# Relay-Timer.net
KiCad netlist of a schematic drawn in EAGLE
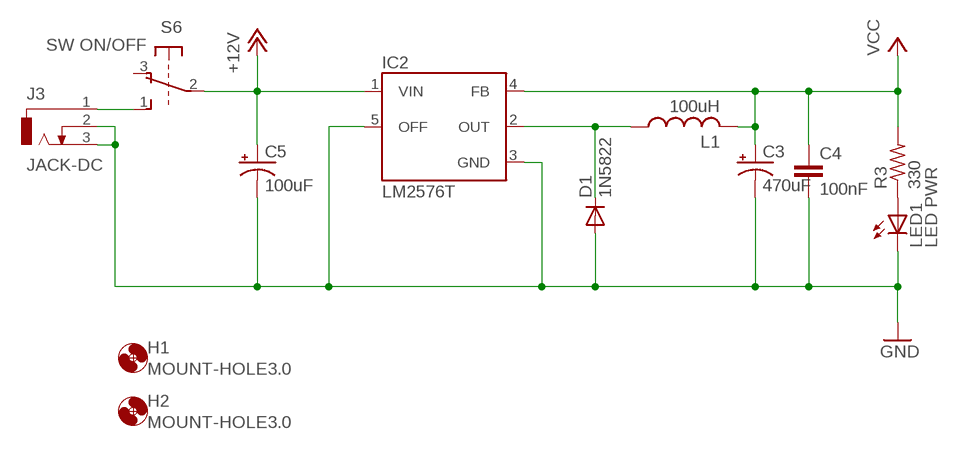
[diagram p0: schematic, sheet 1]
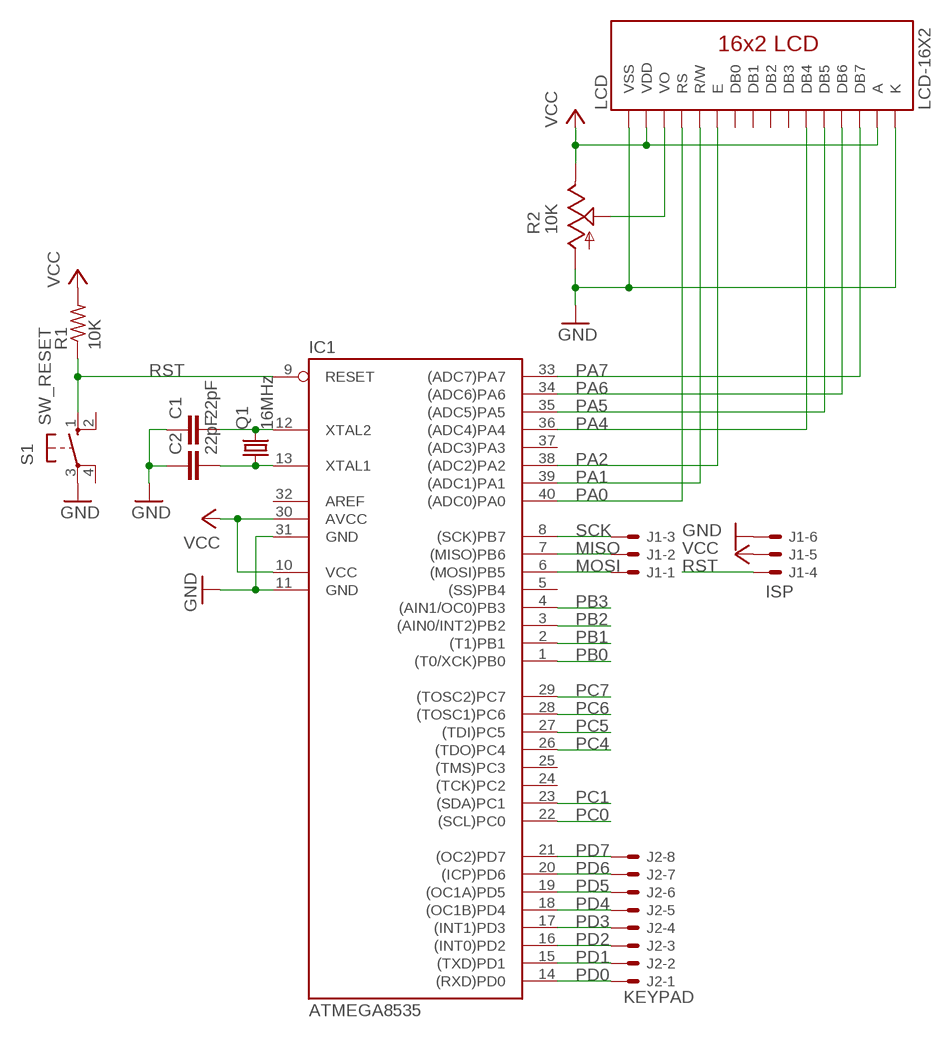
[diagram p1: schematic, sheet 2]
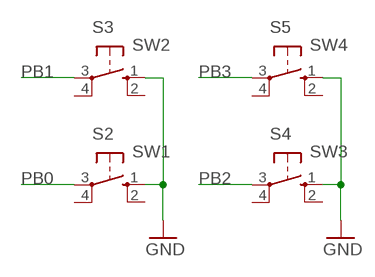
[diagram p2: schematic, sheet 3]
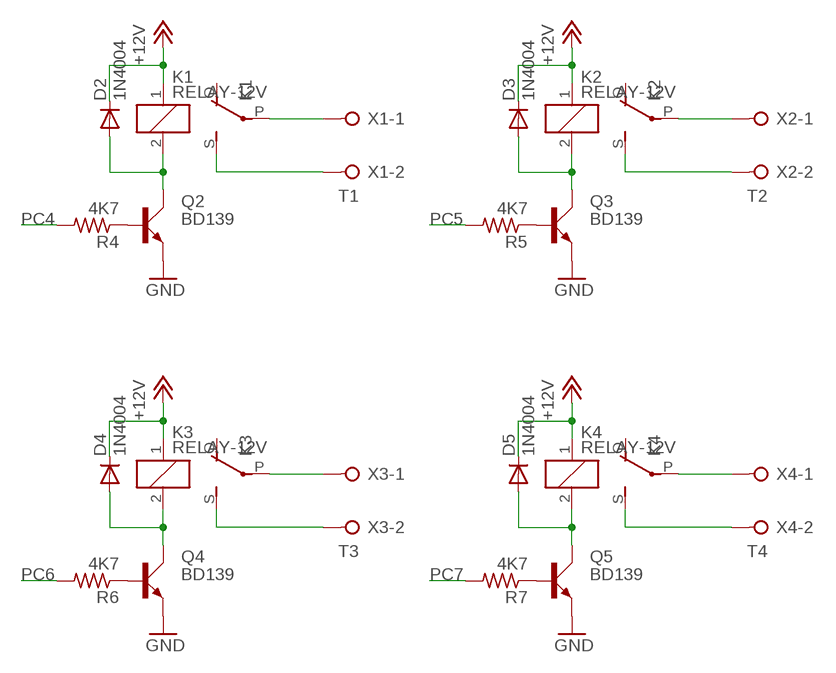
[diagram p3: schematic, sheet 4]
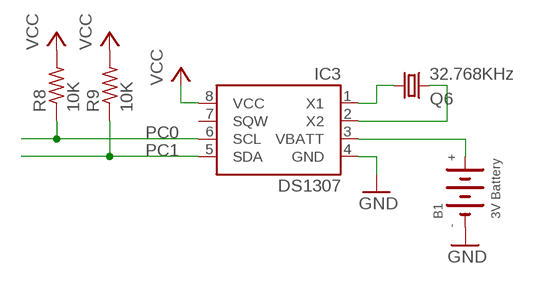
[diagram p4: schematic, sheet 5]

(export (version "E")
  (design (tool "Eeschema 10.0.6"))
  (components
    (comp (ref "C3")
      (value "470uF")
      (footprint "eagle-import:E3,5-8")
      (libsource (lib "eagle-import") (part "CAPACITOR-POLARE3.5-8"))
    )
    (comp (ref "C4")
      (value "100nF")
      (footprint "eagle-import:C025-024X044")
      (libsource (lib "eagle-import") (part "CAPACITOR-NONPOLAR025-024X044"))
    )
    (comp (ref "C5")
      (value "100uF")
      (footprint "eagle-import:E2,5-6")
      (libsource (lib "eagle-import") (part "CAPACITOR-POLARE2.5-6"))
    )
    (comp (ref "D1")
      (value "1N5822")
      (footprint "eagle-import:DO201-15")
      (libsource (lib "eagle-import") (part "DIODE-1N5822"))
    )
    (comp (ref "H1")
      (value "MOUNT-HOLE3.0")
      (footprint "eagle-import:3,0")
      (libsource (lib "eagle-import") (part "MOUNT-HOLE3.0"))
    )
    (comp (ref "H2")
      (value "MOUNT-HOLE3.0")
      (footprint "eagle-import:3,0")
      (libsource (lib "eagle-import") (part "MOUNT-HOLE3.0"))
    )
    (comp (ref "IC2")
      (value "LM2576T")
      (footprint "eagle-import:TO220-5")
      (libsource (lib "eagle-import") (part "LM2576T"))
    )
    (comp (ref "J3")
      (value "JACK-DC")
      (footprint "eagle-import:DCJ0202")
      (libsource (lib "eagle-import") (part "JACK-DC"))
    )
    (comp (ref "L1")
      (value "100uH")
      (footprint "eagle-import:TJ3-U2")
      (libsource (lib "eagle-import") (part "INDUCTORTJ3-U2"))
    )
    (comp (ref "LED1")
      (value "LED PWR")
      (footprint "eagle-import:LED3MM")
      (libsource (lib "eagle-import") (part "LED3MM"))
    )
    (comp (ref "R3")
      (value "330")
      (footprint "eagle-import:0204_7")
      (libsource (lib "eagle-import") (part "RESISTOR0204/7"))
    )
    (comp (ref "S6")
      (value "SW ON/OFF")
      (footprint "eagle-import:9077-2")
      (libsource (lib "eagle-import") (part "SWITCH-DETENT"))
    )
    (comp (ref "D2")
      (value "1N4004")
      (footprint "eagle-import:DO41-10")
      (libsource (lib "eagle-import") (part "DIODE-1N4004"))
    )
    (comp (ref "D3")
      (value "1N4004")
      (footprint "eagle-import:DO41-10")
      (libsource (lib "eagle-import") (part "DIODE-1N4004"))
    )
    (comp (ref "D4")
      (value "1N4004")
      (footprint "eagle-import:DO41-10")
      (libsource (lib "eagle-import") (part "DIODE-1N4004"))
    )
    (comp (ref "D5")
      (value "1N4004")
      (footprint "eagle-import:DO41-10")
      (libsource (lib "eagle-import") (part "DIODE-1N4004"))
    )
    (comp (ref "K1")
      (value "RELAY-12V")
      (footprint "eagle-import:G5LE")
      (libsource (lib "eagle-import") (part "G5L"))
    )
    (comp (ref "K2")
      (value "RELAY-12V")
      (footprint "eagle-import:G5LE")
      (libsource (lib "eagle-import") (part "G5L"))
    )
    (comp (ref "K3")
      (value "RELAY-12V")
      (footprint "eagle-import:G5LE")
      (libsource (lib "eagle-import") (part "G5L"))
    )
    (comp (ref "K4")
      (value "RELAY-12V")
      (footprint "eagle-import:G5LE")
      (libsource (lib "eagle-import") (part "G5L"))
    )
    (comp (ref "Q2")
      (value "BD139")
      (footprint "eagle-import:TO126AV")
      (libsource (lib "eagle-import") (part "BD139"))
    )
    (comp (ref "Q3")
      (value "BD139")
      (footprint "eagle-import:TO126AV")
      (libsource (lib "eagle-import") (part "BD139"))
    )
    (comp (ref "Q4")
      (value "BD139")
      (footprint "eagle-import:TO126AV")
      (libsource (lib "eagle-import") (part "BD139"))
    )
    (comp (ref "Q5")
      (value "BD139")
      (footprint "eagle-import:TO126AV")
      (libsource (lib "eagle-import") (part "BD139"))
    )
    (comp (ref "R4")
      (value "4K7")
      (footprint "eagle-import:0204_7")
      (libsource (lib "eagle-import") (part "RESISTOR0204/7"))
    )
    (comp (ref "R5")
      (value "4K7")
      (footprint "eagle-import:0204_7")
      (libsource (lib "eagle-import") (part "RESISTOR0204/7"))
    )
    (comp (ref "R6")
      (value "4K7")
      (footprint "eagle-import:0204_7")
      (libsource (lib "eagle-import") (part "RESISTOR0204/7"))
    )
    (comp (ref "R7")
      (value "4K7")
      (footprint "eagle-import:0204_7")
      (libsource (lib "eagle-import") (part "RESISTOR0204/7"))
    )
    (comp (ref "X1")
      (value "T1")
      (footprint "eagle-import:W237-132")
      (libsource (lib "eagle-import") (part "W237-02P"))
    )
    (comp (ref "X2")
      (value "T2")
      (footprint "eagle-import:W237-132")
      (libsource (lib "eagle-import") (part "W237-02P"))
    )
    (comp (ref "X3")
      (value "T3")
      (footprint "eagle-import:W237-132")
      (libsource (lib "eagle-import") (part "W237-02P"))
    )
    (comp (ref "X4")
      (value "T4")
      (footprint "eagle-import:W237-132")
      (libsource (lib "eagle-import") (part "W237-02P"))
    )
    (comp (ref "S2")
      (value "SW1")
      (footprint "eagle-import:B3F-10XX")
      (fields (field (name "MPN") "B3F-1000"))
      (libsource (lib "eagle-import") (part "SW-PUSHBUTTON"))
    )
    (comp (ref "S3")
      (value "SW2")
      (footprint "eagle-import:B3F-10XX")
      (fields (field (name "MPN") "B3F-1000"))
      (libsource (lib "eagle-import") (part "SW-PUSHBUTTON"))
    )
    (comp (ref "S4")
      (value "SW3")
      (footprint "eagle-import:B3F-10XX")
      (fields (field (name "MPN") "B3F-1000"))
      (libsource (lib "eagle-import") (part "SW-PUSHBUTTON"))
    )
    (comp (ref "S5")
      (value "SW4")
      (footprint "eagle-import:B3F-10XX")
      (fields (field (name "MPN") "B3F-1000"))
      (libsource (lib "eagle-import") (part "SW-PUSHBUTTON"))
    )
    (comp (ref "B1")
      (value "3V Battery")
      (footprint "eagle-import:CR2032")
      (libsource (lib "eagle-import") (part "BATTERYCR2032"))
    )
    (comp (ref "IC3")
      (value "DS1307")
      (footprint "eagle-import:DIP08")
      (libsource (lib "eagle-import") (part "DS1307"))
    )
    (comp (ref "Q6")
      (value "32.768KHz")
      (footprint "eagle-import:TC26H")
      (libsource (lib "eagle-import") (part "crystal_CRYSTALTC26H"))
    )
    (comp (ref "R8")
      (value "10K")
      (footprint "eagle-import:0204_7")
      (libsource (lib "eagle-import") (part "RESISTOR0204/7"))
    )
    (comp (ref "R9")
      (value "10K")
      (footprint "eagle-import:0204_7")
      (libsource (lib "eagle-import") (part "RESISTOR0204/7"))
    )
    (comp (ref "C1")
      (value "22pF")
      (footprint "eagle-import:C025-024X044")
      (libsource (lib "eagle-import") (part "CAPACITOR-NONPOLAR025-024X044"))
    )
    (comp (ref "C2")
      (value "22pF")
      (footprint "eagle-import:C025-024X044")
      (libsource (lib "eagle-import") (part "CAPACITOR-NONPOLAR025-024X044"))
    )
    (comp (ref "IC1")
      (value "ATMEGA8535")
      (footprint "eagle-import:DIL40")
      (fields (field (name "MPN") "ATMEGA32-16PU"))
      (libsource (lib "eagle-import") (part "ATMEGA8535/16/32"))
    )
    (comp (ref "J1")
      (value "ISP")
      (footprint "eagle-import:6410-06")
      (libsource (lib "eagle-import") (part "CON_MOLEX-?-0627-2061"))
    )
    (comp (ref "J2")
      (value "KEYPAD")
      (footprint "eagle-import:6410-08")
      (libsource (lib "eagle-import") (part "CON_MOLEX-?-0827-2081"))
    )
    (comp (ref "LCD")
      (value "LCD-16X2")
      (footprint "eagle-import:LCD-16X2")
      (libsource (lib "eagle-import") (part "LCD-16X2"))
    )
    (comp (ref "Q1")
      (value "16MHz")
      (footprint "eagle-import:HC49_S")
      (libsource (lib "eagle-import") (part "CRYSTALHC49S"))
    )
    (comp (ref "R1")
      (value "10K")
      (footprint "eagle-import:0204_7")
      (libsource (lib "eagle-import") (part "RESISTOR0204/7"))
    )
    (comp (ref "R2")
      (value "10K")
      (footprint "eagle-import:CA6V")
      (libsource (lib "eagle-import") (part "TRIMPOTCA6V"))
    )
    (comp (ref "S1")
      (value "SW_RESET")
      (footprint "eagle-import:B3F-10XX")
      (fields (field (name "MPN") "B3F-1000"))
      (libsource (lib "eagle-import") (part "SW-PUSHBUTTON"))
    )
  )
  (nets
    (net (code "1") (name "+12V") (class "Default")
      (node (ref "C5") (pin "+") (pinfunction "+_+") (pintype "passive"))
      (node (ref "D2") (pin "C") (pinfunction "C_C") (pintype "passive"))
      (node (ref "D3") (pin "C") (pinfunction "C_C") (pintype "passive"))
      (node (ref "D4") (pin "C") (pinfunction "C_C") (pintype "passive"))
      (node (ref "D5") (pin "C") (pinfunction "C_C") (pintype "passive"))
      (node (ref "IC2") (pin "1") (pinfunction "VIN_1") (pintype "power_in"))
      (node (ref "K1") (pin "1") (pinfunction "1_1") (pintype "passive"))
      (node (ref "K2") (pin "1") (pinfunction "1_1") (pintype "passive"))
      (node (ref "K3") (pin "1") (pinfunction "1_1") (pintype "passive"))
      (node (ref "K4") (pin "1") (pinfunction "1_1") (pintype "passive"))
      (node (ref "S6") (pin "2") (pinfunction "P_2") (pintype "passive"))
    )
    (net (code "2") (name "GND") (class "Default")
      (node (ref "B1") (pin "-") (pinfunction "-_-") (pintype "passive"))
      (node (ref "C1") (pin "1") (pinfunction "1_1") (pintype "passive"))
      (node (ref "C2") (pin "1") (pinfunction "1_1") (pintype "passive"))
      (node (ref "C3") (pin "-") (pinfunction "-_-") (pintype "passive"))
      (node (ref "C4") (pin "2") (pinfunction "2_2") (pintype "passive"))
      (node (ref "C5") (pin "-") (pinfunction "-_-") (pintype "passive"))
      (node (ref "D1") (pin "A") (pinfunction "A_A") (pintype "passive"))
      (node (ref "IC1") (pin "11") (pinfunction "GND_11") (pintype "power_in"))
      (node (ref "IC1") (pin "31") (pinfunction "GND_31") (pintype "power_in"))
      (node (ref "IC2") (pin "3") (pinfunction "GND_3") (pintype "power_in"))
      (node (ref "IC2") (pin "5") (pinfunction "OFF_5") (pintype "input"))
      (node (ref "IC3") (pin "4") (pinfunction "GND_4") (pintype "bidirectional"))
      (node (ref "J1") (pin "6") (pinfunction "S_6") (pintype "passive"))
      (node (ref "J3") (pin "2") (pinfunction "2_2") (pintype "passive"))
      (node (ref "J3") (pin "3") (pinfunction "3_3") (pintype "passive"))
      (node (ref "LCD") (pin "1") (pinfunction "VSS_1") (pintype "power_in"))
      (node (ref "LCD") (pin "16") (pinfunction "K_16") (pintype "power_in"))
      (node (ref "LED1") (pin "K") (pinfunction "C_K") (pintype "passive"))
      (node (ref "Q2") (pin "E") (pinfunction "E_E") (pintype "passive"))
      (node (ref "Q3") (pin "E") (pinfunction "E_E") (pintype "passive"))
      (node (ref "Q4") (pin "E") (pinfunction "E_E") (pintype "passive"))
      (node (ref "Q5") (pin "E") (pinfunction "E_E") (pintype "passive"))
      (node (ref "R2") (pin "A") (pinfunction "A_A") (pintype "passive"))
      (node (ref "S1") (pin "3") (pinfunction "P_3") (pintype "passive"))
      (node (ref "S2") (pin "1") (pinfunction "S_1") (pintype "passive"))
      (node (ref "S3") (pin "1") (pinfunction "S_1") (pintype "passive"))
      (node (ref "S4") (pin "1") (pinfunction "S_1") (pintype "passive"))
      (node (ref "S5") (pin "1") (pinfunction "S_1") (pintype "passive"))
    )
    (net (code "3") (name "MISO") (class "Default")
      (node (ref "IC1") (pin "7") (pinfunction "(MISO)PB6_7") (pintype "bidirectional"))
      (node (ref "J1") (pin "2") (pinfunction "S_2") (pintype "passive"))
    )
    (net (code "4") (name "MOSI") (class "Default")
      (node (ref "IC1") (pin "6") (pinfunction "(MOSI)PB5_6") (pintype "bidirectional"))
      (node (ref "J1") (pin "1") (pinfunction "S_1") (pintype "passive"))
    )
    (net (code "5") (name "Net-(D2-PadA)") (class "Default")
      (node (ref "D2") (pin "A") (pinfunction "A_A") (pintype "passive"))
      (node (ref "K1") (pin "2") (pinfunction "2_2") (pintype "passive"))
      (node (ref "Q2") (pin "C") (pinfunction "C_C") (pintype "passive"))
    )
    (net (code "6") (name "Net-(D3-PadA)") (class "Default")
      (node (ref "D3") (pin "A") (pinfunction "A_A") (pintype "passive"))
      (node (ref "K2") (pin "2") (pinfunction "2_2") (pintype "passive"))
      (node (ref "Q3") (pin "C") (pinfunction "C_C") (pintype "passive"))
    )
    (net (code "7") (name "Net-(D4-PadA)") (class "Default")
      (node (ref "D4") (pin "A") (pinfunction "A_A") (pintype "passive"))
      (node (ref "K3") (pin "2") (pinfunction "2_2") (pintype "passive"))
      (node (ref "Q4") (pin "C") (pinfunction "C_C") (pintype "passive"))
    )
    (net (code "8") (name "Net-(D5-PadA)") (class "Default")
      (node (ref "D5") (pin "A") (pinfunction "A_A") (pintype "passive"))
      (node (ref "K4") (pin "2") (pinfunction "2_2") (pintype "passive"))
      (node (ref "Q5") (pin "C") (pinfunction "C_C") (pintype "passive"))
    )
    (net (code "9") (name "Net-(IC1-XTAL1)") (class "Default")
      (node (ref "C2") (pin "2") (pinfunction "2_2") (pintype "passive"))
      (node (ref "IC1") (pin "13") (pinfunction "XTAL1_13") (pintype "bidirectional"))
      (node (ref "Q1") (pin "1") (pinfunction "1_1") (pintype "passive"))
    )
    (net (code "10") (name "Net-(IC1-XTAL2)") (class "Default")
      (node (ref "C1") (pin "2") (pinfunction "2_2") (pintype "passive"))
      (node (ref "IC1") (pin "12") (pinfunction "XTAL2_12") (pintype "bidirectional"))
      (node (ref "Q1") (pin "2") (pinfunction "2_2") (pintype "passive"))
    )
    (net (code "11") (name "Net-(IC2-OUT)") (class "Default")
      (node (ref "D1") (pin "C") (pinfunction "C_C") (pintype "passive"))
      (node (ref "IC2") (pin "2") (pinfunction "OUT_2") (pintype "output"))
      (node (ref "L1") (pin "1") (pinfunction "1_1") (pintype "passive"))
    )
    (net (code "12") (name "Net-(IC3-VBATT)") (class "Default")
      (node (ref "B1") (pin "+") (pinfunction "+_+") (pintype "passive"))
      (node (ref "IC3") (pin "3") (pinfunction "VBATT_3") (pintype "bidirectional"))
    )
    (net (code "13") (name "Net-(IC3-X1)") (class "Default")
      (node (ref "IC3") (pin "1") (pinfunction "X1_1") (pintype "bidirectional"))
      (node (ref "Q6") (pin "1") (pinfunction "1_1") (pintype "passive"))
    )
    (net (code "14") (name "Net-(IC3-X2)") (class "Default")
      (node (ref "IC3") (pin "2") (pinfunction "X2_2") (pintype "bidirectional"))
      (node (ref "Q6") (pin "2") (pinfunction "2_2") (pintype "passive"))
    )
    (net (code "15") (name "Net-(LCD-VO)") (class "Default")
      (node (ref "LCD") (pin "3") (pinfunction "VO_3") (pintype "bidirectional"))
      (node (ref "R2") (pin "S") (pinfunction "S_S") (pintype "passive"))
    )
    (net (code "16") (name "Net-(LED1-PadA)") (class "Default")
      (node (ref "LED1") (pin "A") (pinfunction "A_A") (pintype "passive"))
      (node (ref "R3") (pin "1") (pinfunction "1_1") (pintype "passive"))
    )
    (net (code "17") (name "Net-(Q2-PadB)") (class "Default")
      (node (ref "Q2") (pin "B") (pinfunction "B_B") (pintype "passive"))
      (node (ref "R4") (pin "1") (pinfunction "1_1") (pintype "passive"))
    )
    (net (code "18") (name "Net-(Q3-PadB)") (class "Default")
      (node (ref "Q3") (pin "B") (pinfunction "B_B") (pintype "passive"))
      (node (ref "R5") (pin "1") (pinfunction "1_1") (pintype "passive"))
    )
    (net (code "19") (name "Net-(Q4-PadB)") (class "Default")
      (node (ref "Q4") (pin "B") (pinfunction "B_B") (pintype "passive"))
      (node (ref "R6") (pin "1") (pinfunction "1_1") (pintype "passive"))
    )
    (net (code "20") (name "Net-(Q5-PadB)") (class "Default")
      (node (ref "Q5") (pin "B") (pinfunction "B_B") (pintype "passive"))
      (node (ref "R7") (pin "1") (pinfunction "1_1") (pintype "passive"))
    )
    (net (code "21") (name "Net-(S6-S)") (class "Default")
      (node (ref "J3") (pin "1") (pinfunction "1_1") (pintype "passive"))
      (node (ref "S6") (pin "1") (pinfunction "S_1") (pintype "passive"))
    )
    (net (code "22") (name "Net-(X1A-KL)") (class "Default")
      (node (ref "K1") (pin "P") (pinfunction "P_P") (pintype "passive"))
      (node (ref "X1") (pin "1") (pinfunction "KL_1") (pintype "passive"))
    )
    (net (code "23") (name "Net-(X1B-KL)") (class "Default")
      (node (ref "K1") (pin "S") (pinfunction "S_S") (pintype "passive"))
      (node (ref "X1") (pin "2") (pinfunction "KL_2") (pintype "passive"))
    )
    (net (code "24") (name "Net-(X2A-KL)") (class "Default")
      (node (ref "K2") (pin "P") (pinfunction "P_P") (pintype "passive"))
      (node (ref "X2") (pin "1") (pinfunction "KL_1") (pintype "passive"))
    )
    (net (code "25") (name "Net-(X2B-KL)") (class "Default")
      (node (ref "K2") (pin "S") (pinfunction "S_S") (pintype "passive"))
      (node (ref "X2") (pin "2") (pinfunction "KL_2") (pintype "passive"))
    )
    (net (code "26") (name "Net-(X3A-KL)") (class "Default")
      (node (ref "K3") (pin "P") (pinfunction "P_P") (pintype "passive"))
      (node (ref "X3") (pin "1") (pinfunction "KL_1") (pintype "passive"))
    )
    (net (code "27") (name "Net-(X3B-KL)") (class "Default")
      (node (ref "K3") (pin "S") (pinfunction "S_S") (pintype "passive"))
      (node (ref "X3") (pin "2") (pinfunction "KL_2") (pintype "passive"))
    )
    (net (code "28") (name "Net-(X4A-KL)") (class "Default")
      (node (ref "K4") (pin "P") (pinfunction "P_P") (pintype "passive"))
      (node (ref "X4") (pin "1") (pinfunction "KL_1") (pintype "passive"))
    )
    (net (code "29") (name "Net-(X4B-KL)") (class "Default")
      (node (ref "K4") (pin "S") (pinfunction "S_S") (pintype "passive"))
      (node (ref "X4") (pin "2") (pinfunction "KL_2") (pintype "passive"))
    )
    (net (code "30") (name "PA0") (class "Default")
      (node (ref "IC1") (pin "40") (pinfunction "(ADC0)PA0_40") (pintype "bidirectional"))
      (node (ref "LCD") (pin "4") (pinfunction "RS_4") (pintype "input"))
    )
    (net (code "31") (name "PA1") (class "Default")
      (node (ref "IC1") (pin "39") (pinfunction "(ADC1)PA1_39") (pintype "bidirectional"))
      (node (ref "LCD") (pin "5") (pinfunction "R/W_5") (pintype "input"))
    )
    (net (code "32") (name "PA2") (class "Default")
      (node (ref "IC1") (pin "38") (pinfunction "(ADC2)PA2_38") (pintype "bidirectional"))
      (node (ref "LCD") (pin "6") (pinfunction "E_6") (pintype "input"))
    )
    (net (code "33") (name "PA4") (class "Default")
      (node (ref "IC1") (pin "36") (pinfunction "(ADC4)PA4_36") (pintype "bidirectional"))
      (node (ref "LCD") (pin "11") (pinfunction "DB4_11") (pintype "bidirectional"))
    )
    (net (code "34") (name "PA5") (class "Default")
      (node (ref "IC1") (pin "35") (pinfunction "(ADC5)PA5_35") (pintype "bidirectional"))
      (node (ref "LCD") (pin "12") (pinfunction "DB5_12") (pintype "bidirectional"))
    )
    (net (code "35") (name "PA6") (class "Default")
      (node (ref "IC1") (pin "34") (pinfunction "(ADC6)PA6_34") (pintype "bidirectional"))
      (node (ref "LCD") (pin "13") (pinfunction "DB6_13") (pintype "bidirectional"))
    )
    (net (code "36") (name "PA7") (class "Default")
      (node (ref "IC1") (pin "33") (pinfunction "(ADC7)PA7_33") (pintype "bidirectional"))
      (node (ref "LCD") (pin "14") (pinfunction "DB7_14") (pintype "bidirectional"))
    )
    (net (code "37") (name "PB0") (class "Default")
      (node (ref "IC1") (pin "1") (pinfunction "(T0/XCK)PB0_1") (pintype "bidirectional"))
      (node (ref "S2") (pin "3") (pinfunction "P_3") (pintype "passive"))
    )
    (net (code "38") (name "PB1") (class "Default")
      (node (ref "IC1") (pin "2") (pinfunction "(T1)PB1_2") (pintype "bidirectional"))
      (node (ref "S3") (pin "3") (pinfunction "P_3") (pintype "passive"))
    )
    (net (code "39") (name "PB2") (class "Default")
      (node (ref "IC1") (pin "3") (pinfunction "(AIN0/INT2)PB2_3") (pintype "bidirectional"))
      (node (ref "S4") (pin "3") (pinfunction "P_3") (pintype "passive"))
    )
    (net (code "40") (name "PB3") (class "Default")
      (node (ref "IC1") (pin "4") (pinfunction "(AIN1/OC0)PB3_4") (pintype "bidirectional"))
      (node (ref "S5") (pin "3") (pinfunction "P_3") (pintype "passive"))
    )
    (net (code "41") (name "PC0") (class "Default")
      (node (ref "IC1") (pin "22") (pinfunction "(SCL)PC0_22") (pintype "bidirectional"))
      (node (ref "IC3") (pin "6") (pinfunction "SCL_6") (pintype "bidirectional"))
      (node (ref "R8") (pin "1") (pinfunction "1_1") (pintype "passive"))
    )
    (net (code "42") (name "PC1") (class "Default")
      (node (ref "IC1") (pin "23") (pinfunction "(SDA)PC1_23") (pintype "bidirectional"))
      (node (ref "IC3") (pin "5") (pinfunction "SDA_5") (pintype "bidirectional"))
      (node (ref "R9") (pin "1") (pinfunction "1_1") (pintype "passive"))
    )
    (net (code "43") (name "PC4") (class "Default")
      (node (ref "IC1") (pin "26") (pinfunction "(TDO)PC4_26") (pintype "bidirectional"))
      (node (ref "R4") (pin "2") (pinfunction "2_2") (pintype "passive"))
    )
    (net (code "44") (name "PC5") (class "Default")
      (node (ref "IC1") (pin "27") (pinfunction "(TDI)PC5_27") (pintype "bidirectional"))
      (node (ref "R5") (pin "2") (pinfunction "2_2") (pintype "passive"))
    )
    (net (code "45") (name "PC6") (class "Default")
      (node (ref "IC1") (pin "28") (pinfunction "(TOSC1)PC6_28") (pintype "bidirectional"))
      (node (ref "R6") (pin "2") (pinfunction "2_2") (pintype "passive"))
    )
    (net (code "46") (name "PC7") (class "Default")
      (node (ref "IC1") (pin "29") (pinfunction "(TOSC2)PC7_29") (pintype "bidirectional"))
      (node (ref "R7") (pin "2") (pinfunction "2_2") (pintype "passive"))
    )
    (net (code "47") (name "PD0") (class "Default")
      (node (ref "IC1") (pin "14") (pinfunction "(RXD)PD0_14") (pintype "bidirectional"))
      (node (ref "J2") (pin "1") (pinfunction "S_1") (pintype "passive"))
    )
    (net (code "48") (name "PD1") (class "Default")
      (node (ref "IC1") (pin "15") (pinfunction "(TXD)PD1_15") (pintype "bidirectional"))
      (node (ref "J2") (pin "2") (pinfunction "S_2") (pintype "passive"))
    )
    (net (code "49") (name "PD2") (class "Default")
      (node (ref "IC1") (pin "16") (pinfunction "(INT0)PD2_16") (pintype "bidirectional"))
      (node (ref "J2") (pin "3") (pinfunction "S_3") (pintype "passive"))
    )
    (net (code "50") (name "PD3") (class "Default")
      (node (ref "IC1") (pin "17") (pinfunction "(INT1)PD3_17") (pintype "bidirectional"))
      (node (ref "J2") (pin "4") (pinfunction "S_4") (pintype "passive"))
    )
    (net (code "51") (name "PD4") (class "Default")
      (node (ref "IC1") (pin "18") (pinfunction "(OC1B)PD4_18") (pintype "bidirectional"))
      (node (ref "J2") (pin "5") (pinfunction "S_5") (pintype "passive"))
    )
    (net (code "52") (name "PD5") (class "Default")
      (node (ref "IC1") (pin "19") (pinfunction "(OC1A)PD5_19") (pintype "bidirectional"))
      (node (ref "J2") (pin "6") (pinfunction "S_6") (pintype "passive"))
    )
    (net (code "53") (name "PD6") (class "Default")
      (node (ref "IC1") (pin "20") (pinfunction "(ICP)PD6_20") (pintype "bidirectional"))
      (node (ref "J2") (pin "7") (pinfunction "S_7") (pintype "passive"))
    )
    (net (code "54") (name "PD7") (class "Default")
      (node (ref "IC1") (pin "21") (pinfunction "(OC2)PD7_21") (pintype "bidirectional"))
      (node (ref "J2") (pin "8") (pinfunction "S_8") (pintype "passive"))
    )
    (net (code "55") (name "RST") (class "Default")
      (node (ref "IC1") (pin "9") (pinfunction "RESET_9") (pintype "input"))
      (node (ref "J1") (pin "4") (pinfunction "S_4") (pintype "passive"))
      (node (ref "R1") (pin "1") (pinfunction "1_1") (pintype "passive"))
      (node (ref "S1") (pin "1") (pinfunction "S_1") (pintype "passive"))
    )
    (net (code "56") (name "SCK") (class "Default")
      (node (ref "IC1") (pin "8") (pinfunction "(SCK)PB7_8") (pintype "bidirectional"))
      (node (ref "J1") (pin "3") (pinfunction "S_3") (pintype "passive"))
    )
    (net (code "57") (name "VCC") (class "Default")
      (node (ref "C3") (pin "+") (pinfunction "+_+") (pintype "passive"))
      (node (ref "C4") (pin "1") (pinfunction "1_1") (pintype "passive"))
      (node (ref "IC1") (pin "10") (pinfunction "VCC_10") (pintype "power_in"))
      (node (ref "IC1") (pin "30") (pinfunction "AVCC_30") (pintype "power_in"))
      (node (ref "IC2") (pin "4") (pinfunction "FB_4") (pintype "input"))
      (node (ref "IC3") (pin "8") (pinfunction "VCC_8") (pintype "bidirectional"))
      (node (ref "J1") (pin "5") (pinfunction "S_5") (pintype "passive"))
      (node (ref "L1") (pin "2") (pinfunction "2_2") (pintype "passive"))
      (node (ref "LCD") (pin "15") (pinfunction "A_15") (pintype "power_in"))
      (node (ref "LCD") (pin "2") (pinfunction "VDD_2") (pintype "power_in"))
      (node (ref "R1") (pin "2") (pinfunction "2_2") (pintype "passive"))
      (node (ref "R2") (pin "E") (pinfunction "E_E") (pintype "passive"))
      (node (ref "R3") (pin "2") (pinfunction "2_2") (pintype "passive"))
      (node (ref "R8") (pin "2") (pinfunction "2_2") (pintype "passive"))
      (node (ref "R9") (pin "2") (pinfunction "2_2") (pintype "passive"))
    )
    (net (code "58") (name "unconnected-(IC1-(ADC3)PA3-Pad37)") (class "Default")
      (node (ref "IC1") (pin "37") (pinfunction "(ADC3)PA3_37") (pintype "bidirectional"))
    )
    (net (code "59") (name "unconnected-(IC1-(SS)PB4-Pad5)") (class "Default")
      (node (ref "IC1") (pin "5") (pinfunction "(SS)PB4_5") (pintype "bidirectional"))
    )
    (net (code "60") (name "unconnected-(IC1-(TCK)PC2-Pad24)") (class "Default")
      (node (ref "IC1") (pin "24") (pinfunction "(TCK)PC2_24") (pintype "bidirectional"))
    )
    (net (code "61") (name "unconnected-(IC1-(TMS)PC3-Pad25)") (class "Default")
      (node (ref "IC1") (pin "25") (pinfunction "(TMS)PC3_25") (pintype "bidirectional"))
    )
    (net (code "62") (name "unconnected-(IC1-AREF-Pad32)") (class "Default")
      (node (ref "IC1") (pin "32") (pinfunction "AREF_32") (pintype "passive"))
    )
    (net (code "63") (name "unconnected-(IC3-SQW-Pad7)") (class "Default")
      (node (ref "IC3") (pin "7") (pinfunction "SQW_7") (pintype "bidirectional"))
    )
    (net (code "64") (name "unconnected-(K1-PadO)") (class "Default")
      (node (ref "K1") (pin "O") (pinfunction "O_O") (pintype "passive"))
    )
    (net (code "65") (name "unconnected-(K2-PadO)") (class "Default")
      (node (ref "K2") (pin "O") (pinfunction "O_O") (pintype "passive"))
    )
    (net (code "66") (name "unconnected-(K3-PadO)") (class "Default")
      (node (ref "K3") (pin "O") (pinfunction "O_O") (pintype "passive"))
    )
    (net (code "67") (name "unconnected-(K4-PadO)") (class "Default")
      (node (ref "K4") (pin "O") (pinfunction "O_O") (pintype "passive"))
    )
    (net (code "68") (name "unconnected-(LCD-DB0-Pad7)") (class "Default")
      (node (ref "LCD") (pin "7") (pinfunction "DB0_7") (pintype "bidirectional"))
    )
    (net (code "69") (name "unconnected-(LCD-DB1-Pad8)") (class "Default")
      (node (ref "LCD") (pin "8") (pinfunction "DB1_8") (pintype "bidirectional"))
    )
    (net (code "70") (name "unconnected-(LCD-DB2-Pad9)") (class "Default")
      (node (ref "LCD") (pin "9") (pinfunction "DB2_9") (pintype "bidirectional"))
    )
    (net (code "71") (name "unconnected-(LCD-DB3-Pad10)") (class "Default")
      (node (ref "LCD") (pin "10") (pinfunction "DB3_10") (pintype "bidirectional"))
    )
    (net (code "72") (name "unconnected-(S1-P1-Pad4)") (class "Default")
      (node (ref "S1") (pin "4") (pinfunction "P1_4") (pintype "passive"))
    )
    (net (code "73") (name "unconnected-(S1-S1-Pad2)") (class "Default")
      (node (ref "S1") (pin "2") (pinfunction "S1_2") (pintype "passive"))
    )
    (net (code "74") (name "unconnected-(S2-P1-Pad4)") (class "Default")
      (node (ref "S2") (pin "4") (pinfunction "P1_4") (pintype "passive"))
    )
    (net (code "75") (name "unconnected-(S2-S1-Pad2)") (class "Default")
      (node (ref "S2") (pin "2") (pinfunction "S1_2") (pintype "passive"))
    )
    (net (code "76") (name "unconnected-(S3-P1-Pad4)") (class "Default")
      (node (ref "S3") (pin "4") (pinfunction "P1_4") (pintype "passive"))
    )
    (net (code "77") (name "unconnected-(S3-S1-Pad2)") (class "Default")
      (node (ref "S3") (pin "2") (pinfunction "S1_2") (pintype "passive"))
    )
    (net (code "78") (name "unconnected-(S4-P1-Pad4)") (class "Default")
      (node (ref "S4") (pin "4") (pinfunction "P1_4") (pintype "passive"))
    )
    (net (code "79") (name "unconnected-(S4-S1-Pad2)") (class "Default")
      (node (ref "S4") (pin "2") (pinfunction "S1_2") (pintype "passive"))
    )
    (net (code "80") (name "unconnected-(S5-P1-Pad4)") (class "Default")
      (node (ref "S5") (pin "4") (pinfunction "P1_4") (pintype "passive"))
    )
    (net (code "81") (name "unconnected-(S5-S1-Pad2)") (class "Default")
      (node (ref "S5") (pin "2") (pinfunction "S1_2") (pintype "passive"))
    )
    (net (code "82") (name "unconnected-(S6-O-Pad3)") (class "Default")
      (node (ref "S6") (pin "3") (pinfunction "O_3") (pintype "passive"))
    )
  )
)
